# RS485.net
KiCad netlist of a schematic drawn in Altium Designer
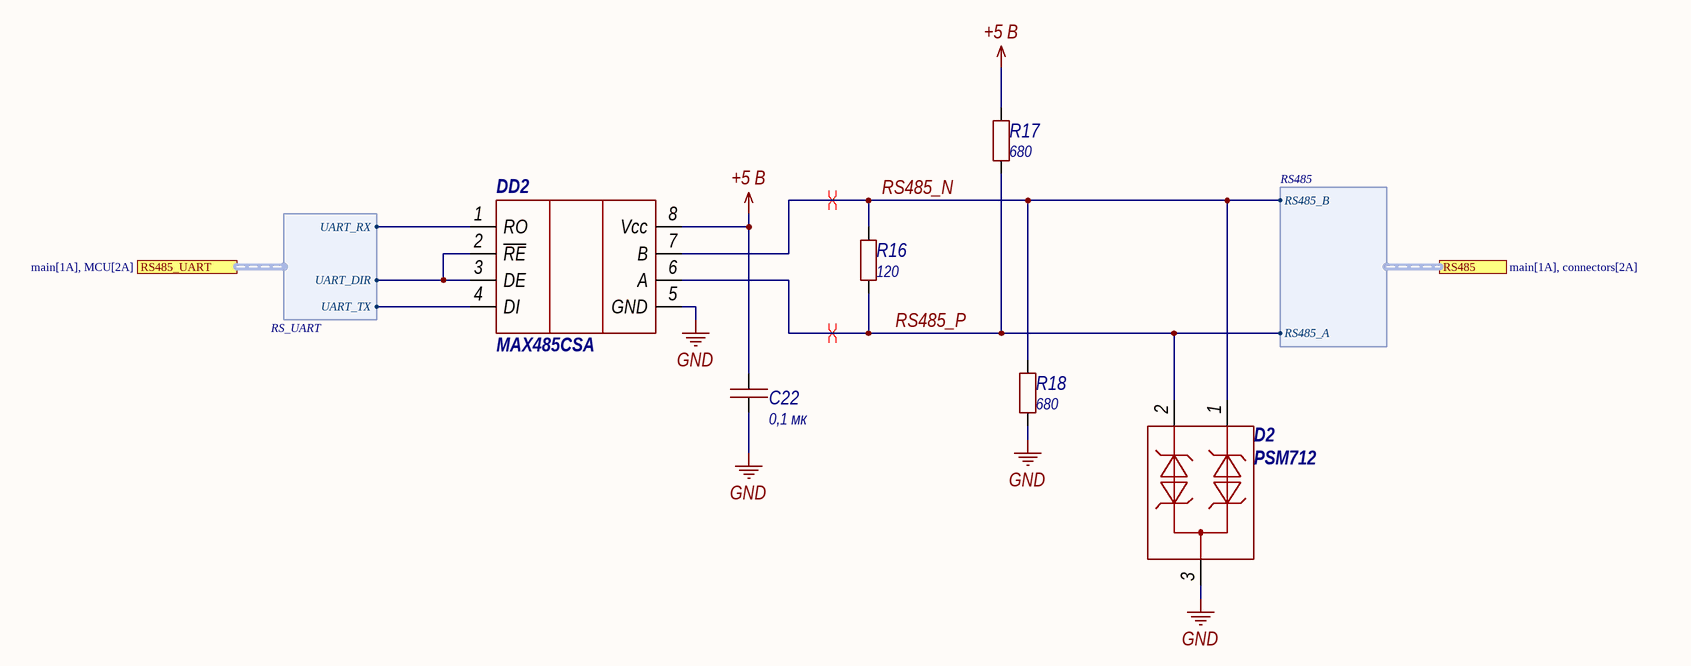
[diagram p0: RS485.SchDoc]

(export (version "E")
  (design (tool "Eeschema 10.0.6"))
  (components
    (comp (ref "C22")
      (value "0,1 мк")
      (footprint "0603C")
      (description "Конденсатор 0603C ёмкостью 0,1 мк 10%, 50 В, X7R")
      (fields (field (name "PART NUMBER") "Capacitor_0,1u_10_50V_X7R_0603C") (field (name "TOLERANCE") "10%"))
      (libsource (lib "Hydrolib") (part "Capacitor"))
    )
    (comp (ref "D2")
      (value "PSM712")
      (footprint "SOT23-3")
      (description "Защитный диод для линии RS-485")
      (libsource (lib "Hydrolib") (part "TVS_2_2dir"))
    )
    (comp (ref "DD2")
      (value "MAX485CSA")
      (footprint "SOIC-8")
      (description "RS-485 приёмопередатчик")
      (libsource (lib "Hydrolib") (part "MAX485CSA"))
    )
    (comp (ref "R16")
      (value "120")
      (footprint "1206R")
      (description "Резистор номиналом 120 Ом 1%")
      (fields (field (name "PART NUMBER") "Resistor_120_1_0603") (field (name "TOLERANCE") "1%"))
      (libsource (lib "Hydrolib") (part "Resistor"))
    )
    (comp (ref "R17")
      (value "680")
      (footprint "0603R")
      (description "Резистор номиналом 680 Ом 1%")
      (fields (field (name "PART NUMBER") "Resistor_680_1_0603") (field (name "TOLERANCE") "1%"))
      (libsource (lib "Hydrolib") (part "Resistor"))
    )
    (comp (ref "R18")
      (value "680")
      (footprint "0603R")
      (description "Резистор номиналом 680 Ом 1%")
      (fields (field (name "PART NUMBER") "Resistor_680_1_0603") (field (name "TOLERANCE") "1%"))
      (libsource (lib "Hydrolib") (part "Resistor"))
    )
  )
  (nets
    (net (code "3") (name "+5 В") (class "Default")
      (node (ref "C22") (pin "2") (pinfunction "2_2") (pintype "passive"))
      (node (ref "DD2") (pin "8") (pinfunction "Vcc_8") (pintype "passive"))
      (node (ref "R17") (pin "2") (pinfunction "2_2") (pintype "passive"))
    )
    (net (code "4") (name "/RS485_N") (class "Default")
      (node (ref "D2") (pin "1") (pinfunction "14_1") (pintype "passive"))
      (node (ref "DD2") (pin "7") (pinfunction "B_7") (pintype "passive"))
      (node (ref "R16") (pin "2") (pinfunction "2_2") (pintype "passive"))
      (node (ref "R18") (pin "2") (pinfunction "2_2") (pintype "passive"))
    )
    (net (code "5") (name "/RS485_P") (class "Default")
      (node (ref "D2") (pin "2") (pinfunction "15_2") (pintype "passive"))
      (node (ref "DD2") (pin "6") (pinfunction "A_6") (pintype "passive"))
      (node (ref "R16") (pin "1") (pinfunction "1_1") (pintype "passive"))
      (node (ref "R17") (pin "1") (pinfunction "1_1") (pintype "passive"))
    )
    (net (code "6") (name "/UART_DIR") (class "Default")
      (node (ref "DD2") (pin "2") (pinfunction "RE_2") (pintype "passive"))
      (node (ref "DD2") (pin "3") (pinfunction "DE_3") (pintype "passive"))
    )
    (net (code "7") (name "/UART_RX") (class "Default")
      (node (ref "DD2") (pin "1") (pinfunction "RO_1") (pintype "passive"))
    )
    (net (code "8") (name "/UART_TX") (class "Default")
      (node (ref "DD2") (pin "4") (pinfunction "DI_4") (pintype "passive"))
    )
    (net (code "11") (name "GND") (class "Default")
      (node (ref "C22") (pin "1") (pinfunction "1_1") (pintype "passive"))
      (node (ref "D2") (pin "3") (pinfunction "16_3") (pintype "passive"))
      (node (ref "DD2") (pin "5") (pinfunction "GND_5") (pintype "passive"))
      (node (ref "R18") (pin "1") (pinfunction "1_1") (pintype "passive"))
    )
  )
)
